# design-1.net
KiCad netlist of a schematic drawn in EAGLE
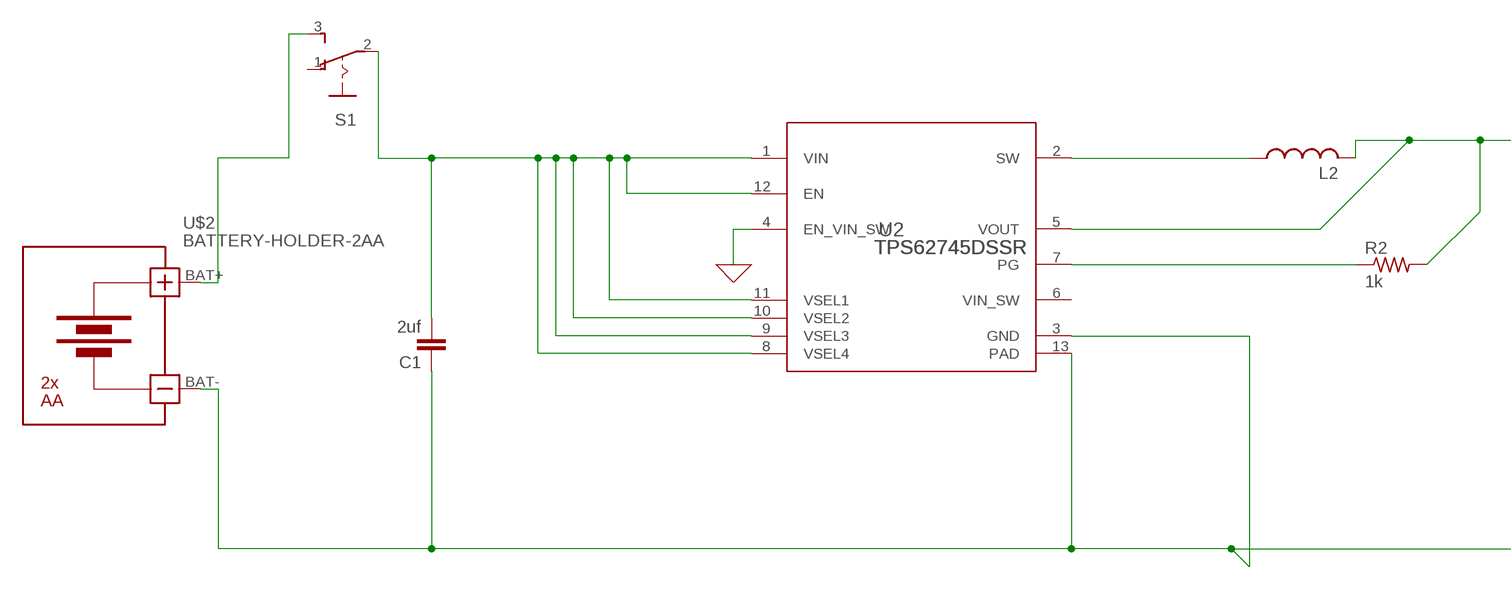
[diagram p0: schematic, sheet 1, part 1 of 2]
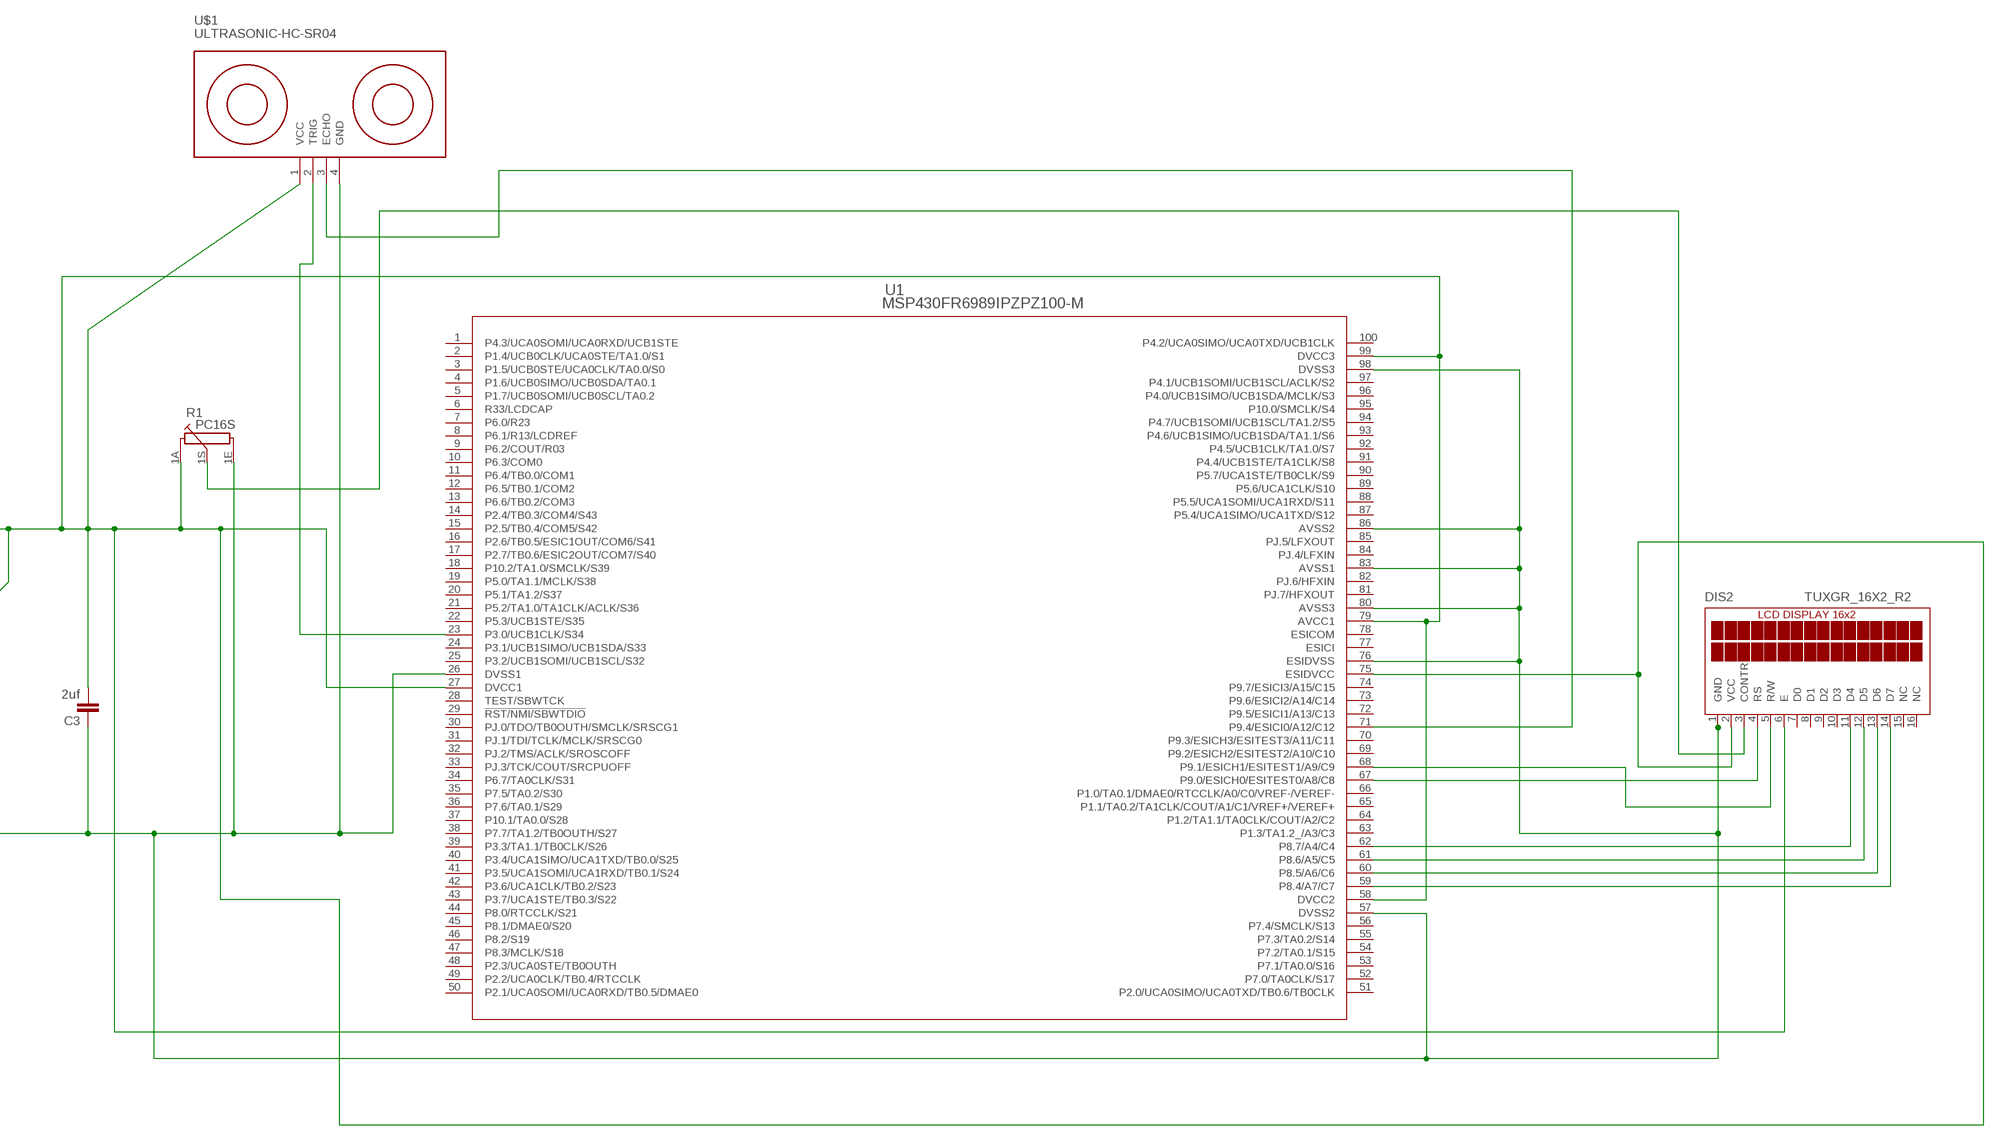
[diagram p1: schematic, sheet 1, part 2 of 2]

(export (version "E")
  (design (tool "Eeschema 10.0.6"))
  (components
    (comp (ref "C1")
      (value "2uf")
      (footprint "eagle-import:C0603")
      (libsource (lib "eagle-import") (part "C-EUC0603"))
    )
    (comp (ref "C3")
      (value "2uf")
      (footprint "eagle-import:C0603")
      (libsource (lib "eagle-import") (part "C-EUC0603"))
    )
    (comp (ref "DIS2")
      (value "TUXGR_16X2_R2")
      (footprint "eagle-import:TUXGR_16X2_R2")
      (libsource (lib "eagle-import") (part "TUXGR_16X2_R2"))
    )
    (comp (ref "L2")
      (value "L-US0204/5")
      (footprint "eagle-import:0204_5")
      (libsource (lib "eagle-import") (part "L-US0204/5"))
    )
    (comp (ref "R1")
      (value "PC16S")
      (footprint "eagle-import:PC16S")
      (libsource (lib "eagle-import") (part "PC16S"))
    )
    (comp (ref "R2")
      (value "1k")
      (footprint "eagle-import:R0603")
      (libsource (lib "eagle-import") (part "R-US_R0603"))
    )
    (comp (ref "S1")
      (value "255SB")
      (footprint "eagle-import:255SB")
      (libsource (lib "eagle-import") (part "255SB"))
    )
    (comp (ref "U$1")
      (value "ULTRASONIC-HC-SR04")
      (footprint "eagle-import:ULTRASONIC-HC-SR04")
      (libsource (lib "eagle-import") (part "ULTRASONIC-HC-SR04"))
    )
    (comp (ref "U$2")
      (value "BATTERY-HOLDER-2AA")
      (footprint "eagle-import:BATTERY-HOLDER-2AA")
      (libsource (lib "eagle-import") (part "BATTERY-HOLDER-2AA"))
    )
    (comp (ref "U1")
      (value "MSP430FR6989IPZPZ100-M")
      (footprint "eagle-import:PZ100-M")
      (fields (field (name "MANUFACTURER_PART_NUMBER") "MSP430FR6989IPZ"))
      (libsource (lib "eagle-import") (part "MSP430FR6989IPZPZ100-M"))
    )
    (comp (ref "U2")
      (value "TPS62745DSSR")
      (footprint "eagle-import:DSS0012A")
      (libsource (lib "eagle-import") (part "TPS62745DSSR"))
    )
  )
  (nets
    (net (code "1") (name "/VIN_SW") (class "Default")
      (node (ref "U2") (pin "6") (pinfunction "VIN_SW_6") (pintype "power_in"))
    )
    (net (code "2") (name "GND") (class "Default")
      (node (ref "U2") (pin "4") (pinfunction "EN_VIN_SW_4") (pintype "input"))
    )
    (net (code "3") (name "Net-(DIS2-CONTR)") (class "Default")
      (node (ref "DIS2") (pin "3") (pinfunction "CONTR_3") (pintype "input"))
      (node (ref "R1") (pin "1S") (pinfunction "1S_1S") (pintype "passive"))
    )
    (net (code "4") (name "Net-(DIS2-D4)") (class "Default")
      (node (ref "DIS2") (pin "11") (pinfunction "D4_11") (pintype "input"))
      (node (ref "U1") (pin "62") (pinfunction "P8.7/A4/C4_62") (pintype "bidirectional"))
    )
    (net (code "5") (name "Net-(DIS2-D5)") (class "Default")
      (node (ref "DIS2") (pin "12") (pinfunction "D5_12") (pintype "input"))
      (node (ref "U1") (pin "61") (pinfunction "P8.6/A5/C5_61") (pintype "bidirectional"))
    )
    (net (code "6") (name "Net-(DIS2-D6)") (class "Default")
      (node (ref "DIS2") (pin "13") (pinfunction "D6_13") (pintype "input"))
      (node (ref "U1") (pin "60") (pinfunction "P8.5/A6/C6_60") (pintype "bidirectional"))
    )
    (net (code "7") (name "Net-(DIS2-D7)") (class "Default")
      (node (ref "DIS2") (pin "14") (pinfunction "D7_14") (pintype "input"))
      (node (ref "U1") (pin "59") (pinfunction "P8.4/A7/C7_59") (pintype "bidirectional"))
    )
    (net (code "8") (name "Net-(DIS2-E)") (class "Default")
      (node (ref "C3") (pin "2") (pinfunction "2_2") (pintype "passive"))
      (node (ref "DIS2") (pin "2") (pinfunction "VCC_2") (pintype "power_in"))
      (node (ref "DIS2") (pin "6") (pinfunction "E_6") (pintype "input"))
      (node (ref "L2") (pin "2") (pinfunction "2_2") (pintype "passive"))
      (node (ref "R1") (pin "1A") (pinfunction "1A_1A") (pintype "passive"))
      (node (ref "R2") (pin "2") (pinfunction "2_2") (pintype "passive"))
      (node (ref "U$1") (pin "1") (pinfunction "VCC_1") (pintype "power_in"))
      (node (ref "U1") (pin "27") (pinfunction "DVCC1_27") (pintype "power_in"))
      (node (ref "U1") (pin "58") (pinfunction "DVCC2_58") (pintype "power_in"))
      (node (ref "U1") (pin "75") (pinfunction "ESIDVCC_75") (pintype "power_in"))
      (node (ref "U1") (pin "79") (pinfunction "AVCC1_79") (pintype "power_in"))
      (node (ref "U1") (pin "99") (pinfunction "DVCC3_99") (pintype "power_in"))
      (node (ref "U2") (pin "5") (pinfunction "VOUT_5") (pintype "input"))
    )
    (net (code "9") (name "Net-(DIS2-GND)") (class "Default")
      (node (ref "C1") (pin "1") (pinfunction "1_1") (pintype "passive"))
      (node (ref "C3") (pin "1") (pinfunction "1_1") (pintype "passive"))
      (node (ref "DIS2") (pin "1") (pinfunction "GND_1") (pintype "power_in"))
      (node (ref "R1") (pin "1E") (pinfunction "1E_1E") (pintype "passive"))
      (node (ref "U$1") (pin "4") (pinfunction "GND_4") (pintype "power_in"))
      (node (ref "U$2") (pin "BAT-") (pinfunction "BAT-_BAT-") (pintype "power_in"))
      (node (ref "U1") (pin "26") (pinfunction "DVSS1_26") (pintype "power_in"))
      (node (ref "U1") (pin "57") (pinfunction "DVSS2_57") (pintype "power_in"))
      (node (ref "U1") (pin "76") (pinfunction "ESIDVSS_76") (pintype "power_in"))
      (node (ref "U1") (pin "80") (pinfunction "AVSS3_80") (pintype "power_in"))
      (node (ref "U1") (pin "83") (pinfunction "AVSS1_83") (pintype "power_in"))
      (node (ref "U1") (pin "86") (pinfunction "AVSS2_86") (pintype "power_in"))
      (node (ref "U1") (pin "98") (pinfunction "DVSS3_98") (pintype "power_in"))
      (node (ref "U2") (pin "13") (pinfunction "PAD_13") (pintype "passive"))
      (node (ref "U2") (pin "3") (pinfunction "GND_3") (pintype "power_in"))
    )
    (net (code "10") (name "Net-(DIS2-RS)") (class "Default")
      (node (ref "DIS2") (pin "4") (pinfunction "RS_4") (pintype "input"))
      (node (ref "U1") (pin "67") (pinfunction "P9.0/ESICH0/ESITEST0/A8/C8_67") (pintype "bidirectional"))
    )
    (net (code "11") (name "Net-(DIS2-R{slash}W)") (class "Default")
      (node (ref "DIS2") (pin "5") (pinfunction "R/W_5") (pintype "input"))
      (node (ref "U1") (pin "68") (pinfunction "P9.1/ESICH1/ESITEST1/A9/C9_68") (pintype "bidirectional"))
    )
    (net (code "12") (name "Net-(S1-P)") (class "Default")
      (node (ref "C1") (pin "2") (pinfunction "2_2") (pintype "passive"))
      (node (ref "S1") (pin "2") (pinfunction "P_2") (pintype "passive"))
      (node (ref "U2") (pin "1") (pinfunction "VIN_1") (pintype "power_in"))
      (node (ref "U2") (pin "10") (pinfunction "VSEL2_10") (pintype "input"))
      (node (ref "U2") (pin "11") (pinfunction "VSEL1_11") (pintype "input"))
      (node (ref "U2") (pin "12") (pinfunction "EN_12") (pintype "input"))
      (node (ref "U2") (pin "8") (pinfunction "VSEL4_8") (pintype "input"))
      (node (ref "U2") (pin "9") (pinfunction "VSEL3_9") (pintype "input"))
    )
    (net (code "13") (name "Net-(S1-S)") (class "Default")
      (node (ref "S1") (pin "3") (pinfunction "S_3") (pintype "passive"))
      (node (ref "U$2") (pin "BAT+") (pinfunction "BAT+_BAT+") (pintype "power_in"))
    )
    (net (code "14") (name "Net-(U$1-ECHO)") (class "Default")
      (node (ref "U$1") (pin "3") (pinfunction "ECHO_3") (pintype "output"))
      (node (ref "U1") (pin "71") (pinfunction "P9.4/ESICI0/A12/C12_71") (pintype "bidirectional"))
    )
    (net (code "15") (name "Net-(U$1-TRIG)") (class "Default")
      (node (ref "U$1") (pin "2") (pinfunction "TRIG_2") (pintype "input"))
      (node (ref "U1") (pin "23") (pinfunction "P3.0/UCB1CLK/S34_23") (pintype "bidirectional"))
    )
    (net (code "16") (name "Net-(U2-PG)") (class "Default")
      (node (ref "R2") (pin "1") (pinfunction "1_1") (pintype "passive"))
      (node (ref "U2") (pin "7") (pinfunction "PG_7") (pintype "open_collector"))
    )
    (net (code "17") (name "Net-(U2-SW)") (class "Default")
      (node (ref "L2") (pin "1") (pinfunction "1_1") (pintype "passive"))
      (node (ref "U2") (pin "2") (pinfunction "SW_2") (pintype "power_in"))
    )
    (net (code "18") (name "unconnected-(DIS2-D0-Pad7)") (class "Default")
      (node (ref "DIS2") (pin "7") (pinfunction "D0_7") (pintype "input"))
    )
    (net (code "19") (name "unconnected-(DIS2-D1-Pad8)") (class "Default")
      (node (ref "DIS2") (pin "8") (pinfunction "D1_8") (pintype "input"))
    )
    (net (code "20") (name "unconnected-(DIS2-D2-Pad9)") (class "Default")
      (node (ref "DIS2") (pin "9") (pinfunction "D2_9") (pintype "input"))
    )
    (net (code "21") (name "unconnected-(DIS2-D3-Pad10)") (class "Default")
      (node (ref "DIS2") (pin "10") (pinfunction "D3_10") (pintype "input"))
    )
    (net (code "22") (name "unconnected-(DIS2-NC-Pad15)") (class "Default")
      (node (ref "DIS2") (pin "15") (pinfunction "NC_15") (pintype "no_connect"))
    )
    (net (code "23") (name "unconnected-(DIS2-NC-Pad16)") (class "Default")
      (node (ref "DIS2") (pin "16") (pinfunction "NC_16") (pintype "no_connect"))
    )
    (net (code "24") (name "unconnected-(S1-O-Pad1)") (class "Default")
      (node (ref "S1") (pin "1") (pinfunction "O_1") (pintype "passive"))
    )
    (net (code "25") (name "unconnected-(U1-ESICI-Pad77)") (class "Default")
      (node (ref "U1") (pin "77") (pinfunction "ESICI_77") (pintype "input"))
    )
    (net (code "26") (name "unconnected-(U1-ESICOM-Pad78)") (class "Default")
      (node (ref "U1") (pin "78") (pinfunction "ESICOM_78") (pintype "passive"))
    )
    (net (code "27") (name "unconnected-(U1-P1.0{slash}TA0.1{slash}DMAE0{slash}RTCCLK{slash}A0{slash}C0{slash}VREF-{slash}VEREF--Pad66)") (class "Default")
      (node (ref "U1") (pin "66") (pinfunction "P1.0/TA0.1/DMAE0/RTCCLK/A0/C0/VREF-/VEREF-_66") (pintype "bidirectional"))
    )
    (net (code "28") (name "unconnected-(U1-P1.1{slash}TA0.2{slash}TA1CLK{slash}COUT{slash}A1{slash}C1{slash}VREF+{slash}VEREF+-Pad65)") (class "Default")
      (node (ref "U1") (pin "65") (pinfunction "P1.1/TA0.2/TA1CLK/COUT/A1/C1/VREF+/VEREF+_65") (pintype "bidirectional"))
    )
    (net (code "29") (name "unconnected-(U1-P1.2{slash}TA1.1{slash}TA0CLK{slash}COUT{slash}A2{slash}C2-Pad64)") (class "Default")
      (node (ref "U1") (pin "64") (pinfunction "P1.2/TA1.1/TA0CLK/COUT/A2/C2_64") (pintype "bidirectional"))
    )
    (net (code "30") (name "unconnected-(U1-P1.3{slash}TA1.2_{slash}A3{slash}C3-Pad63)") (class "Default")
      (node (ref "U1") (pin "63") (pinfunction "P1.3/TA1.2_/A3/C3_63") (pintype "bidirectional"))
    )
    (net (code "31") (name "unconnected-(U1-P1.4{slash}UCB0CLK{slash}UCA0STE{slash}TA1.0{slash}S1-Pad2)") (class "Default")
      (node (ref "U1") (pin "2") (pinfunction "P1.4/UCB0CLK/UCA0STE/TA1.0/S1_2") (pintype "bidirectional"))
    )
    (net (code "32") (name "unconnected-(U1-P1.5{slash}UCB0STE{slash}UCA0CLK{slash}TA0.0{slash}S0-Pad3)") (class "Default")
      (node (ref "U1") (pin "3") (pinfunction "P1.5/UCB0STE/UCA0CLK/TA0.0/S0_3") (pintype "bidirectional"))
    )
    (net (code "33") (name "unconnected-(U1-P1.6{slash}UCB0SIMO{slash}UCB0SDA{slash}TA0.1-Pad4)") (class "Default")
      (node (ref "U1") (pin "4") (pinfunction "P1.6/UCB0SIMO/UCB0SDA/TA0.1_4") (pintype "bidirectional"))
    )
    (net (code "34") (name "unconnected-(U1-P1.7{slash}UCB0SOMI{slash}UCB0SCL{slash}TA0.2-Pad5)") (class "Default")
      (node (ref "U1") (pin "5") (pinfunction "P1.7/UCB0SOMI/UCB0SCL/TA0.2_5") (pintype "bidirectional"))
    )
    (net (code "35") (name "unconnected-(U1-P2.0{slash}UCA0SIMO{slash}UCA0TXD{slash}TB0.6{slash}TB0CLK-Pad51)") (class "Default")
      (node (ref "U1") (pin "51") (pinfunction "P2.0/UCA0SIMO/UCA0TXD/TB0.6/TB0CLK_51") (pintype "bidirectional"))
    )
    (net (code "36") (name "unconnected-(U1-P2.1{slash}UCA0SOMI{slash}UCA0RXD{slash}TB0.5{slash}DMAE0-Pad50)") (class "Default")
      (node (ref "U1") (pin "50") (pinfunction "P2.1/UCA0SOMI/UCA0RXD/TB0.5/DMAE0_50") (pintype "bidirectional"))
    )
    (net (code "37") (name "unconnected-(U1-P2.2{slash}UCA0CLK{slash}TB0.4{slash}RTCCLK-Pad49)") (class "Default")
      (node (ref "U1") (pin "49") (pinfunction "P2.2/UCA0CLK/TB0.4/RTCCLK_49") (pintype "bidirectional"))
    )
    (net (code "38") (name "unconnected-(U1-P2.3{slash}UCA0STE{slash}TB0OUTH-Pad48)") (class "Default")
      (node (ref "U1") (pin "48") (pinfunction "P2.3/UCA0STE/TB0OUTH_48") (pintype "bidirectional"))
    )
    (net (code "39") (name "unconnected-(U1-P2.4{slash}TB0.3{slash}COM4{slash}S43-Pad14)") (class "Default")
      (node (ref "U1") (pin "14") (pinfunction "P2.4/TB0.3/COM4/S43_14") (pintype "bidirectional"))
    )
    (net (code "40") (name "unconnected-(U1-P2.5{slash}TB0.4{slash}COM5{slash}S42-Pad15)") (class "Default")
      (node (ref "U1") (pin "15") (pinfunction "P2.5/TB0.4/COM5/S42_15") (pintype "bidirectional"))
    )
    (net (code "41") (name "unconnected-(U1-P2.6{slash}TB0.5{slash}ESIC1OUT{slash}COM6{slash}S41-Pad16)") (class "Default")
      (node (ref "U1") (pin "16") (pinfunction "P2.6/TB0.5/ESIC1OUT/COM6/S41_16") (pintype "bidirectional"))
    )
    (net (code "42") (name "unconnected-(U1-P2.7{slash}TB0.6{slash}ESIC2OUT{slash}COM7{slash}S40-Pad17)") (class "Default")
      (node (ref "U1") (pin "17") (pinfunction "P2.7/TB0.6/ESIC2OUT/COM7/S40_17") (pintype "bidirectional"))
    )
    (net (code "43") (name "unconnected-(U1-P3.1{slash}UCB1SIMO{slash}UCB1SDA{slash}S33-Pad24)") (class "Default")
      (node (ref "U1") (pin "24") (pinfunction "P3.1/UCB1SIMO/UCB1SDA/S33_24") (pintype "bidirectional"))
    )
    (net (code "44") (name "unconnected-(U1-P3.2{slash}UCB1SOMI{slash}UCB1SCL{slash}S32-Pad25)") (class "Default")
      (node (ref "U1") (pin "25") (pinfunction "P3.2/UCB1SOMI/UCB1SCL/S32_25") (pintype "bidirectional"))
    )
    (net (code "45") (name "unconnected-(U1-P3.3{slash}TA1.1{slash}TB0CLK{slash}S26-Pad39)") (class "Default")
      (node (ref "U1") (pin "39") (pinfunction "P3.3/TA1.1/TB0CLK/S26_39") (pintype "bidirectional"))
    )
    (net (code "46") (name "unconnected-(U1-P3.4{slash}UCA1SIMO{slash}UCA1TXD{slash}TB0.0{slash}S25-Pad40)") (class "Default")
      (node (ref "U1") (pin "40") (pinfunction "P3.4/UCA1SIMO/UCA1TXD/TB0.0/S25_40") (pintype "bidirectional"))
    )
    (net (code "47") (name "unconnected-(U1-P3.5{slash}UCA1SOMI{slash}UCA1RXD{slash}TB0.1{slash}S24-Pad41)") (class "Default")
      (node (ref "U1") (pin "41") (pinfunction "P3.5/UCA1SOMI/UCA1RXD/TB0.1/S24_41") (pintype "bidirectional"))
    )
    (net (code "48") (name "unconnected-(U1-P3.6{slash}UCA1CLK{slash}TB0.2{slash}S23-Pad42)") (class "Default")
      (node (ref "U1") (pin "42") (pinfunction "P3.6/UCA1CLK/TB0.2/S23_42") (pintype "bidirectional"))
    )
    (net (code "49") (name "unconnected-(U1-P3.7{slash}UCA1STE{slash}TB0.3{slash}S22-Pad43)") (class "Default")
      (node (ref "U1") (pin "43") (pinfunction "P3.7/UCA1STE/TB0.3/S22_43") (pintype "bidirectional"))
    )
    (net (code "50") (name "unconnected-(U1-P4.0{slash}UCB1SIMO{slash}UCB1SDA{slash}MCLK{slash}S3-Pad96)") (class "Default")
      (node (ref "U1") (pin "96") (pinfunction "P4.0/UCB1SIMO/UCB1SDA/MCLK/S3_96") (pintype "bidirectional"))
    )
    (net (code "51") (name "unconnected-(U1-P4.1{slash}UCB1SOMI{slash}UCB1SCL{slash}ACLK{slash}S2-Pad97)") (class "Default")
      (node (ref "U1") (pin "97") (pinfunction "P4.1/UCB1SOMI/UCB1SCL/ACLK/S2_97") (pintype "bidirectional"))
    )
    (net (code "52") (name "unconnected-(U1-P4.2{slash}UCA0SIMO{slash}UCA0TXD{slash}UCB1CLK-Pad100)") (class "Default")
      (node (ref "U1") (pin "100") (pinfunction "P4.2/UCA0SIMO/UCA0TXD/UCB1CLK_100") (pintype "bidirectional"))
    )
    (net (code "53") (name "unconnected-(U1-P4.3{slash}UCA0SOMI{slash}UCA0RXD{slash}UCB1STE-Pad1)") (class "Default")
      (node (ref "U1") (pin "1") (pinfunction "P4.3/UCA0SOMI/UCA0RXD/UCB1STE_1") (pintype "bidirectional"))
    )
    (net (code "54") (name "unconnected-(U1-P4.4{slash}UCB1STE{slash}TA1CLK{slash}S8-Pad91)") (class "Default")
      (node (ref "U1") (pin "91") (pinfunction "P4.4/UCB1STE/TA1CLK/S8_91") (pintype "bidirectional"))
    )
    (net (code "55") (name "unconnected-(U1-P4.5{slash}UCB1CLK{slash}TA1.0{slash}S7-Pad92)") (class "Default")
      (node (ref "U1") (pin "92") (pinfunction "P4.5/UCB1CLK/TA1.0/S7_92") (pintype "bidirectional"))
    )
    (net (code "56") (name "unconnected-(U1-P4.6{slash}UCB1SIMO{slash}UCB1SDA{slash}TA1.1{slash}S6-Pad93)") (class "Default")
      (node (ref "U1") (pin "93") (pinfunction "P4.6/UCB1SIMO/UCB1SDA/TA1.1/S6_93") (pintype "bidirectional"))
    )
    (net (code "57") (name "unconnected-(U1-P4.7{slash}UCB1SOMI{slash}UCB1SCL{slash}TA1.2{slash}S5-Pad94)") (class "Default")
      (node (ref "U1") (pin "94") (pinfunction "P4.7/UCB1SOMI/UCB1SCL/TA1.2/S5_94") (pintype "bidirectional"))
    )
    (net (code "58") (name "unconnected-(U1-P5.0{slash}TA1.1{slash}MCLK{slash}S38-Pad19)") (class "Default")
      (node (ref "U1") (pin "19") (pinfunction "P5.0/TA1.1/MCLK/S38_19") (pintype "bidirectional"))
    )
    (net (code "59") (name "unconnected-(U1-P5.1{slash}TA1.2{slash}S37-Pad20)") (class "Default")
      (node (ref "U1") (pin "20") (pinfunction "P5.1/TA1.2/S37_20") (pintype "bidirectional"))
    )
    (net (code "60") (name "unconnected-(U1-P5.2{slash}TA1.0{slash}TA1CLK{slash}ACLK{slash}S36-Pad21)") (class "Default")
      (node (ref "U1") (pin "21") (pinfunction "P5.2/TA1.0/TA1CLK/ACLK/S36_21") (pintype "bidirectional"))
    )
    (net (code "61") (name "unconnected-(U1-P5.3{slash}UCB1STE{slash}S35-Pad22)") (class "Default")
      (node (ref "U1") (pin "22") (pinfunction "P5.3/UCB1STE/S35_22") (pintype "bidirectional"))
    )
    (net (code "62") (name "unconnected-(U1-P5.4{slash}UCA1SIMO{slash}UCA1TXD{slash}S12-Pad87)") (class "Default")
      (node (ref "U1") (pin "87") (pinfunction "P5.4/UCA1SIMO/UCA1TXD/S12_87") (pintype "bidirectional"))
    )
    (net (code "63") (name "unconnected-(U1-P5.5{slash}UCA1SOMI{slash}UCA1RXD{slash}S11-Pad88)") (class "Default")
      (node (ref "U1") (pin "88") (pinfunction "P5.5/UCA1SOMI/UCA1RXD/S11_88") (pintype "bidirectional"))
    )
    (net (code "64") (name "unconnected-(U1-P5.6{slash}UCA1CLK{slash}S10-Pad89)") (class "Default")
      (node (ref "U1") (pin "89") (pinfunction "P5.6/UCA1CLK/S10_89") (pintype "bidirectional"))
    )
    (net (code "65") (name "unconnected-(U1-P5.7{slash}UCA1STE{slash}TB0CLK{slash}S9-Pad90)") (class "Default")
      (node (ref "U1") (pin "90") (pinfunction "P5.7/UCA1STE/TB0CLK/S9_90") (pintype "bidirectional"))
    )
    (net (code "66") (name "unconnected-(U1-P6.0{slash}R23-Pad7)") (class "Default")
      (node (ref "U1") (pin "7") (pinfunction "P6.0/R23_7") (pintype "bidirectional"))
    )
    (net (code "67") (name "unconnected-(U1-P6.1{slash}R13{slash}LCDREF-Pad8)") (class "Default")
      (node (ref "U1") (pin "8") (pinfunction "P6.1/R13/LCDREF_8") (pintype "bidirectional"))
    )
    (net (code "68") (name "unconnected-(U1-P6.2{slash}COUT{slash}R03-Pad9)") (class "Default")
      (node (ref "U1") (pin "9") (pinfunction "P6.2/COUT/R03_9") (pintype "bidirectional"))
    )
    (net (code "69") (name "unconnected-(U1-P6.3{slash}COM0-Pad10)") (class "Default")
      (node (ref "U1") (pin "10") (pinfunction "P6.3/COM0_10") (pintype "bidirectional"))
    )
    (net (code "70") (name "unconnected-(U1-P6.4{slash}TB0.0{slash}COM1-Pad11)") (class "Default")
      (node (ref "U1") (pin "11") (pinfunction "P6.4/TB0.0/COM1_11") (pintype "bidirectional"))
    )
    (net (code "71") (name "unconnected-(U1-P6.5{slash}TB0.1{slash}COM2-Pad12)") (class "Default")
      (node (ref "U1") (pin "12") (pinfunction "P6.5/TB0.1/COM2_12") (pintype "bidirectional"))
    )
    (net (code "72") (name "unconnected-(U1-P6.6{slash}TB0.2{slash}COM3-Pad13)") (class "Default")
      (node (ref "U1") (pin "13") (pinfunction "P6.6/TB0.2/COM3_13") (pintype "bidirectional"))
    )
    (net (code "73") (name "unconnected-(U1-P6.7{slash}TA0CLK{slash}S31-Pad34)") (class "Default")
      (node (ref "U1") (pin "34") (pinfunction "P6.7/TA0CLK/S31_34") (pintype "bidirectional"))
    )
    (net (code "74") (name "unconnected-(U1-P7.0{slash}TA0CLK{slash}S17-Pad52)") (class "Default")
      (node (ref "U1") (pin "52") (pinfunction "P7.0/TA0CLK/S17_52") (pintype "bidirectional"))
    )
    (net (code "75") (name "unconnected-(U1-P7.1{slash}TA0.0{slash}S16-Pad53)") (class "Default")
      (node (ref "U1") (pin "53") (pinfunction "P7.1/TA0.0/S16_53") (pintype "bidirectional"))
    )
    (net (code "76") (name "unconnected-(U1-P7.2{slash}TA0.1{slash}S15-Pad54)") (class "Default")
      (node (ref "U1") (pin "54") (pinfunction "P7.2/TA0.1/S15_54") (pintype "bidirectional"))
    )
    (net (code "77") (name "unconnected-(U1-P7.3{slash}TA0.2{slash}S14-Pad55)") (class "Default")
      (node (ref "U1") (pin "55") (pinfunction "P7.3/TA0.2/S14_55") (pintype "bidirectional"))
    )
    (net (code "78") (name "unconnected-(U1-P7.4{slash}SMCLK{slash}S13-Pad56)") (class "Default")
      (node (ref "U1") (pin "56") (pinfunction "P7.4/SMCLK/S13_56") (pintype "bidirectional"))
    )
    (net (code "79") (name "unconnected-(U1-P7.5{slash}TA0.2{slash}S30-Pad35)") (class "Default")
      (node (ref "U1") (pin "35") (pinfunction "P7.5/TA0.2/S30_35") (pintype "bidirectional"))
    )
    (net (code "80") (name "unconnected-(U1-P7.6{slash}TA0.1{slash}S29-Pad36)") (class "Default")
      (node (ref "U1") (pin "36") (pinfunction "P7.6/TA0.1/S29_36") (pintype "bidirectional"))
    )
    (net (code "81") (name "unconnected-(U1-P7.7{slash}TA1.2{slash}TB0OUTH{slash}S27-Pad38)") (class "Default")
      (node (ref "U1") (pin "38") (pinfunction "P7.7/TA1.2/TB0OUTH/S27_38") (pintype "bidirectional"))
    )
    (net (code "82") (name "unconnected-(U1-P8.0{slash}RTCCLK{slash}S21-Pad44)") (class "Default")
      (node (ref "U1") (pin "44") (pinfunction "P8.0/RTCCLK/S21_44") (pintype "bidirectional"))
    )
    (net (code "83") (name "unconnected-(U1-P8.1{slash}DMAE0{slash}S20-Pad45)") (class "Default")
      (node (ref "U1") (pin "45") (pinfunction "P8.1/DMAE0/S20_45") (pintype "bidirectional"))
    )
    (net (code "84") (name "unconnected-(U1-P8.2{slash}S19-Pad46)") (class "Default")
      (node (ref "U1") (pin "46") (pinfunction "P8.2/S19_46") (pintype "bidirectional"))
    )
    (net (code "85") (name "unconnected-(U1-P8.3{slash}MCLK{slash}S18-Pad47)") (class "Default")
      (node (ref "U1") (pin "47") (pinfunction "P8.3/MCLK/S18_47") (pintype "bidirectional"))
    )
    (net (code "86") (name "unconnected-(U1-P9.2{slash}ESICH2{slash}ESITEST2{slash}A10{slash}C10-Pad69)") (class "Default")
      (node (ref "U1") (pin "69") (pinfunction "P9.2/ESICH2/ESITEST2/A10/C10_69") (pintype "bidirectional"))
    )
    (net (code "87") (name "unconnected-(U1-P9.3{slash}ESICH3{slash}ESITEST3{slash}A11{slash}C11-Pad70)") (class "Default")
      (node (ref "U1") (pin "70") (pinfunction "P9.3/ESICH3/ESITEST3/A11/C11_70") (pintype "bidirectional"))
    )
    (net (code "88") (name "unconnected-(U1-P9.5{slash}ESICI1{slash}A13{slash}C13-Pad72)") (class "Default")
      (node (ref "U1") (pin "72") (pinfunction "P9.5/ESICI1/A13/C13_72") (pintype "bidirectional"))
    )
    (net (code "89") (name "unconnected-(U1-P9.6{slash}ESICI2{slash}A14{slash}C14-Pad73)") (class "Default")
      (node (ref "U1") (pin "73") (pinfunction "P9.6/ESICI2/A14/C14_73") (pintype "bidirectional"))
    )
    (net (code "90") (name "unconnected-(U1-P9.7{slash}ESICI3{slash}A15{slash}C15-Pad74)") (class "Default")
      (node (ref "U1") (pin "74") (pinfunction "P9.7/ESICI3/A15/C15_74") (pintype "bidirectional"))
    )
    (net (code "91") (name "unconnected-(U1-P10.0{slash}SMCLK{slash}S4-Pad95)") (class "Default")
      (node (ref "U1") (pin "95") (pinfunction "P10.0/SMCLK/S4_95") (pintype "bidirectional"))
    )
    (net (code "92") (name "unconnected-(U1-P10.1{slash}TA0.0{slash}S28-Pad37)") (class "Default")
      (node (ref "U1") (pin "37") (pinfunction "P10.1/TA0.0/S28_37") (pintype "bidirectional"))
    )
    (net (code "93") (name "unconnected-(U1-P10.2{slash}TA1.0{slash}SMCLK{slash}S39-Pad18)") (class "Default")
      (node (ref "U1") (pin "18") (pinfunction "P10.2/TA1.0/SMCLK/S39_18") (pintype "bidirectional"))
    )
    (net (code "94") (name "unconnected-(U1-PJ.0{slash}TDO{slash}TB0OUTH{slash}SMCLK{slash}SRSCG1-Pad30)") (class "Default")
      (node (ref "U1") (pin "30") (pinfunction "PJ.0/TDO/TB0OUTH/SMCLK/SRSCG1_30") (pintype "bidirectional"))
    )
    (net (code "95") (name "unconnected-(U1-PJ.1{slash}TDI{slash}TCLK{slash}MCLK{slash}SRSCG0-Pad31)") (class "Default")
      (node (ref "U1") (pin "31") (pinfunction "PJ.1/TDI/TCLK/MCLK/SRSCG0_31") (pintype "bidirectional"))
    )
    (net (code "96") (name "unconnected-(U1-PJ.2{slash}TMS{slash}ACLK{slash}SROSCOFF-Pad32)") (class "Default")
      (node (ref "U1") (pin "32") (pinfunction "PJ.2/TMS/ACLK/SROSCOFF_32") (pintype "bidirectional"))
    )
    (net (code "97") (name "unconnected-(U1-PJ.3{slash}TCK{slash}COUT{slash}SRCPUOFF-Pad33)") (class "Default")
      (node (ref "U1") (pin "33") (pinfunction "PJ.3/TCK/COUT/SRCPUOFF_33") (pintype "bidirectional"))
    )
    (net (code "98") (name "unconnected-(U1-PJ.4{slash}LFXIN-Pad84)") (class "Default")
      (node (ref "U1") (pin "84") (pinfunction "PJ.4/LFXIN_84") (pintype "bidirectional"))
    )
    (net (code "99") (name "unconnected-(U1-PJ.5{slash}LFXOUT-Pad85)") (class "Default")
      (node (ref "U1") (pin "85") (pinfunction "PJ.5/LFXOUT_85") (pintype "bidirectional"))
    )
    (net (code "100") (name "unconnected-(U1-PJ.6{slash}HFXIN-Pad82)") (class "Default")
      (node (ref "U1") (pin "82") (pinfunction "PJ.6/HFXIN_82") (pintype "bidirectional"))
    )
    (net (code "101") (name "unconnected-(U1-PJ.7{slash}HFXOUT-Pad81)") (class "Default")
      (node (ref "U1") (pin "81") (pinfunction "PJ.7/HFXOUT_81") (pintype "bidirectional"))
    )
    (net (code "102") (name "unconnected-(U1-R33{slash}LCDCAP-Pad6)") (class "Default")
      (node (ref "U1") (pin "6") (pinfunction "R33/LCDCAP_6") (pintype "bidirectional"))
    )
    (net (code "103") (name "unconnected-(U1-TEST{slash}SBWTCK-Pad28)") (class "Default")
      (node (ref "U1") (pin "28") (pinfunction "TEST/SBWTCK_28") (pintype "input"))
    )
    (net (code "104") (name "unconnected-(U1-~{RST{slash}NMI{slash}SBWTDIO}-Pad29)") (class "Default")
      (node (ref "U1") (pin "29") (pinfunction "~{RST/NMI/SBWTDIO}_29") (pintype "bidirectional"))
    )
  )
)
